# magicmouth-v0_1-ss.net
KiCad netlist of a schematic drawn in EAGLE
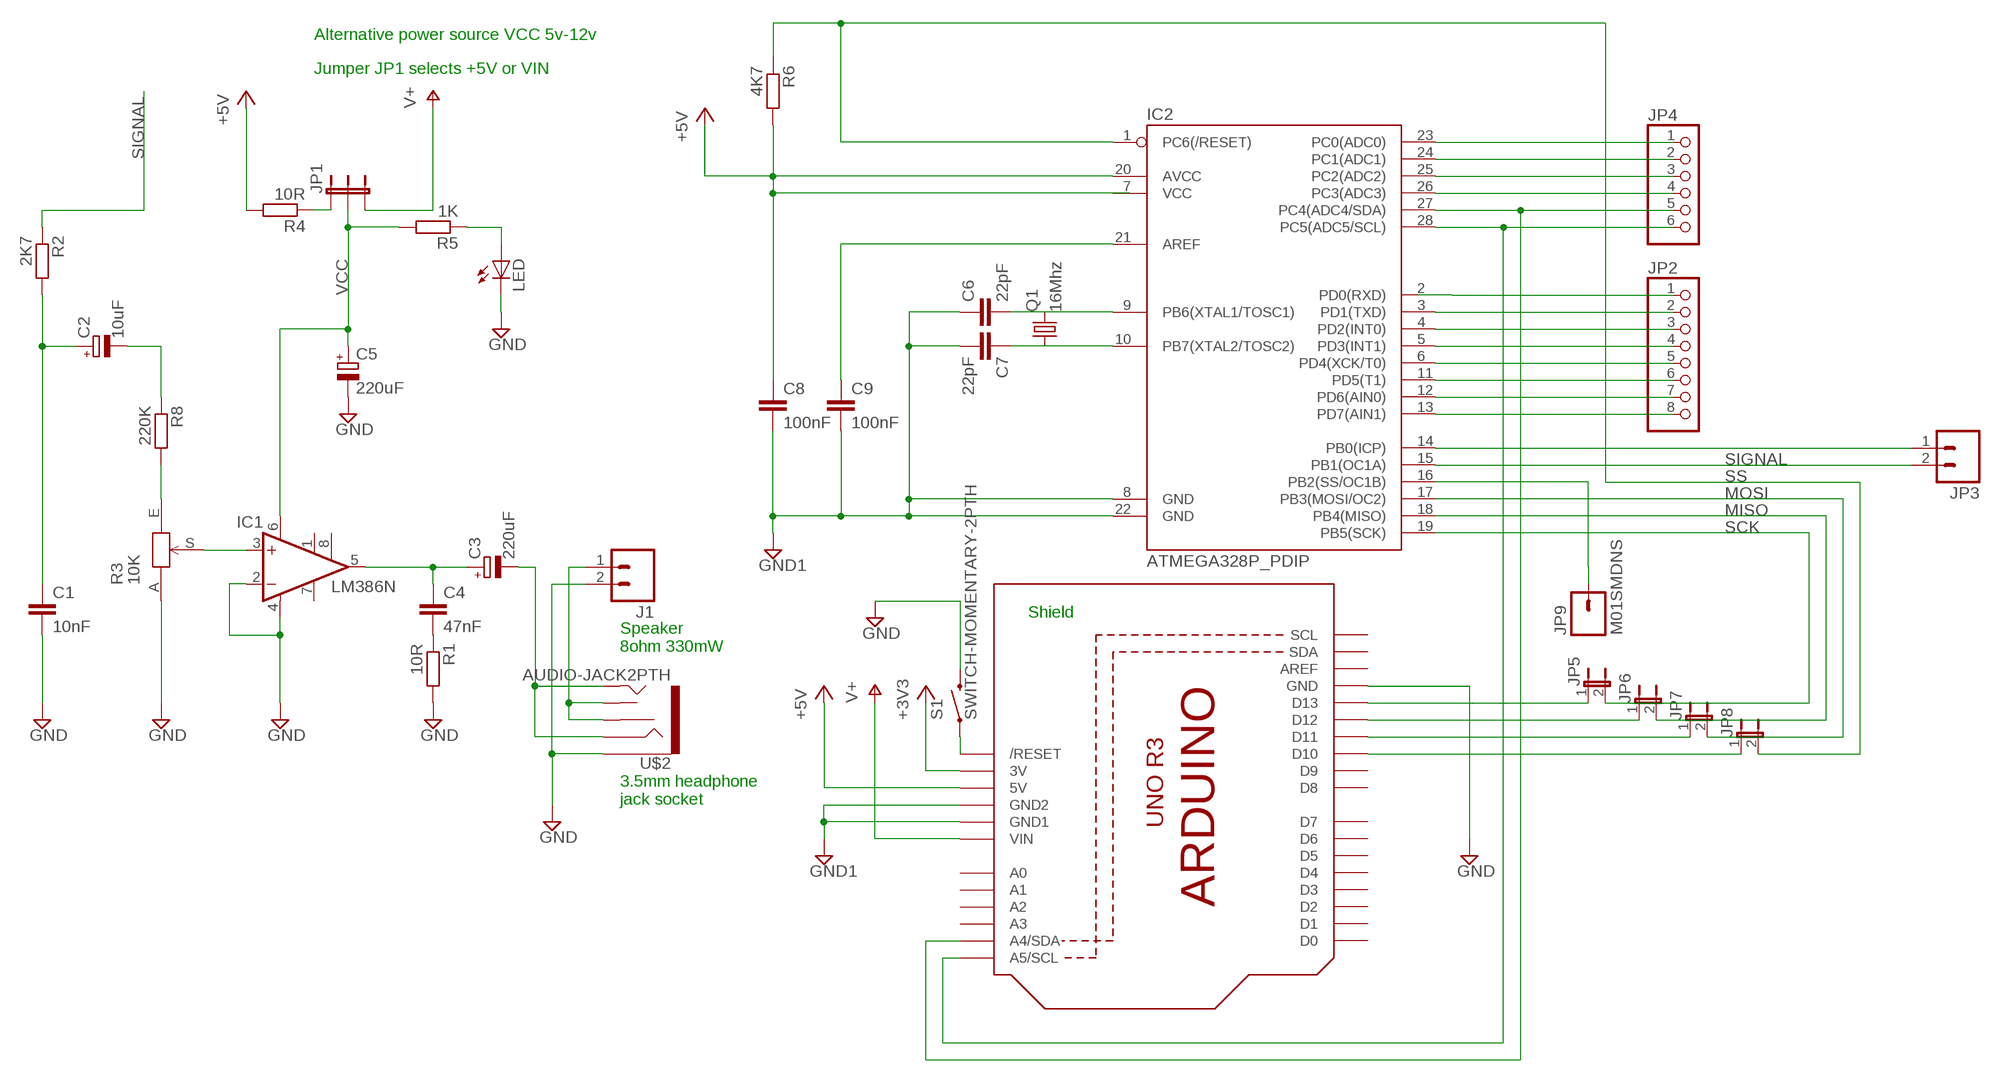
[diagram p0: schematic, sheet 1]

(export (version "E")
  (design (tool "Eeschema 10.0.6"))
  (components
    (comp (ref "C1")
      (value "10nF")
      (footprint "eagle-import:C050-025X075")
      (libsource (lib "eagle-import") (part "resistor_C-EU050-025X075"))
    )
    (comp (ref "C2")
      (value "10uF")
      (footprint "eagle-import:E2,5-7")
      (libsource (lib "eagle-import") (part "CPOL-EUE2.5-7"))
    )
    (comp (ref "C3")
      (value "220uF")
      (footprint "eagle-import:TT5D7L")
      (libsource (lib "eagle-import") (part "CPOL-EUTT5D7L"))
    )
    (comp (ref "C4")
      (value "47nF")
      (footprint "eagle-import:C050-025X075")
      (libsource (lib "eagle-import") (part "resistor_C-EU050-025X075"))
    )
    (comp (ref "C5")
      (value "220uF")
      (footprint "eagle-import:TT5D7L")
      (libsource (lib "eagle-import") (part "CPOL-EUTT5D7L"))
    )
    (comp (ref "C6")
      (value "22pF")
      (footprint "eagle-import:C025-025X050")
      (fields (field (name "CAPACITANCE") "22 pf"))
      (libsource (lib "eagle-import") (part "C-EU025-025X050"))
    )
    (comp (ref "C7")
      (value "22pF")
      (footprint "eagle-import:C025-025X050")
      (fields (field (name "CAPACITANCE") "22 pf"))
      (libsource (lib "eagle-import") (part "C-EU025-025X050"))
    )
    (comp (ref "C8")
      (value "100nF")
      (footprint "eagle-import:C025-025X050")
      (fields (field (name "CAPACITANCE") "10 nF"))
      (libsource (lib "eagle-import") (part "C-EU025-025X050"))
    )
    (comp (ref "C9")
      (value "100nF")
      (footprint "eagle-import:C025-025X050")
      (fields (field (name "CAPACITANCE") "100 nF"))
      (libsource (lib "eagle-import") (part "C-EU025-025X050"))
    )
    (comp (ref "IC1")
      (value "LM386N")
      (footprint "eagle-import:DIL08")
      (libsource (lib "eagle-import") (part "LM386?-N1"))
    )
    (comp (ref "IC2")
      (value "ATMEGA328P_PDIP")
      (footprint "eagle-import:DIL28-3")
      (libsource (lib "eagle-import") (part "ATMEGA328P_PDIP"))
    )
    (comp (ref "J1")
      (value "M023.5MM")
      (footprint "eagle-import:SCREWTERMINAL-3.5MM-2")
      (libsource (lib "eagle-import") (part "M023.5MM"))
    )
    (comp (ref "JP1")
      (value "JUMPER-3PTH")
      (footprint "eagle-import:1X03")
      (libsource (lib "eagle-import") (part "JUMPER-3PTH"))
    )
    (comp (ref "JP2")
      (value "PINHD-1X8CLEANBIG")
      (footprint "eagle-import:1X08-CLEANBIG")
      (libsource (lib "eagle-import") (part "PINHD-1X8CLEANBIG"))
    )
    (comp (ref "JP3")
      (value "M021X02_NO_SILK")
      (footprint "eagle-import:1X02_NO_SILK")
      (libsource (lib "eagle-import") (part "M021X02_NO_SILK"))
    )
    (comp (ref "JP4")
      (value "PINHD-1X6CB")
      (footprint "eagle-import:1X06-CLEANBIG")
      (libsource (lib "eagle-import") (part "PINHD-1X6CB"))
    )
    (comp (ref "JP5")
      (value "JUMPER-2PTH")
      (footprint "eagle-import:1X02")
      (libsource (lib "eagle-import") (part "JUMPER-2PTH"))
    )
    (comp (ref "JP6")
      (value "JUMPER-2PTH")
      (footprint "eagle-import:1X02")
      (libsource (lib "eagle-import") (part "JUMPER-2PTH"))
    )
    (comp (ref "JP7")
      (value "JUMPER-2PTH")
      (footprint "eagle-import:1X02")
      (libsource (lib "eagle-import") (part "JUMPER-2PTH"))
    )
    (comp (ref "JP8")
      (value "JUMPER-2PTH")
      (footprint "eagle-import:1X02")
      (libsource (lib "eagle-import") (part "JUMPER-2PTH"))
    )
    (comp (ref "JP9")
      (value "M01SMDNS")
      (footprint "eagle-import:1X01NS")
      (libsource (lib "eagle-import") (part "M01SMDNS"))
    )
    (comp (ref "LED")
      (value "LED3MM")
      (footprint "eagle-import:LED3MM")
      (libsource (lib "eagle-import") (part "LED3MM"))
    )
    (comp (ref "Q1")
      (value "16Mhz")
      (footprint "eagle-import:HC49_S")
      (libsource (lib "eagle-import") (part "CRYSTALHC49S"))
    )
    (comp (ref "R1")
      (value "10R")
      (footprint "eagle-import:0207_7")
      (libsource (lib "eagle-import") (part "resistor_R-EU_0207/7"))
    )
    (comp (ref "R2")
      (value "2K7")
      (footprint "eagle-import:0207_7")
      (libsource (lib "eagle-import") (part "R-EU_0207/7"))
    )
    (comp (ref "R3")
      (value "10K")
      (footprint "eagle-import:3352T")
      (libsource (lib "eagle-import") (part "TPOT3352"))
    )
    (comp (ref "R4")
      (value "10R")
      (footprint "eagle-import:0207_7")
      (libsource (lib "eagle-import") (part "R-EU_0207/7"))
    )
    (comp (ref "R5")
      (value "1K")
      (footprint "eagle-import:0207_7")
      (libsource (lib "eagle-import") (part "R-EU_0207/7"))
    )
    (comp (ref "R6")
      (value "4K7")
      (footprint "eagle-import:0207_7")
      (fields (field (name "RESISTANCE") "4K7"))
      (libsource (lib "eagle-import") (part "R-EU_0207/7"))
    )
    (comp (ref "R8")
      (value "220K")
      (footprint "eagle-import:0207_7")
      (libsource (lib "eagle-import") (part "R-EU_0207/7"))
    )
    (comp (ref "S1")
      (value "SWITCH-MOMENTARY-2PTH")
      (footprint "eagle-import:TACTILE-PTH")
      (libsource (lib "eagle-import") (part "SWITCH-MOMENTARY-2PTH"))
    )
    (comp (ref "U$2")
      (value "AUDIO-JACK2PTH")
      (footprint "eagle-import:AUDIO-JACK")
      (libsource (lib "eagle-import") (part "AUDIO-JACK2PTH"))
    )
    (comp (ref "U1")
      (value "ARDUINOR3-NOIOREF-NOTEXT")
      (footprint "eagle-import:ARDUINOR3-NOTEXT-NOIOREF")
      (libsource (lib "eagle-import") (part "ARDUINOR3-NOIOREF-NOTEXT"))
    )
  )
  (nets
    (net (code "1") (name "+3V3") (class "Default")
      (node (ref "U1") (pin "3V") (pinfunction "3V_3V") (pintype "power_in"))
    )
    (net (code "2") (name "+5V") (class "Default")
      (node (ref "C8") (pin "1") (pinfunction "1_1") (pintype "passive"))
      (node (ref "IC2") (pin "20") (pinfunction "AVCC_20") (pintype "bidirectional"))
      (node (ref "R4") (pin "2") (pinfunction "2_2") (pintype "passive"))
      (node (ref "R6") (pin "2") (pinfunction "2_2") (pintype "passive"))
      (node (ref "U1") (pin "5V") (pinfunction "5V_5V") (pintype "power_in"))
    )
    (net (code "3") (name "/MISO") (class "Default")
      (node (ref "IC2") (pin "18") (pinfunction "PB4(MISO)_18") (pintype "bidirectional"))
      (node (ref "JP6") (pin "2") (pinfunction "2_2") (pintype "passive"))
    )
    (net (code "4") (name "/MOSI") (class "Default")
      (node (ref "IC2") (pin "17") (pinfunction "PB3(MOSI/OC2)_17") (pintype "bidirectional"))
      (node (ref "JP7") (pin "2") (pinfunction "2_2") (pintype "passive"))
    )
    (net (code "5") (name "/SCK") (class "Default")
      (node (ref "IC2") (pin "19") (pinfunction "PB5(SCK)_19") (pintype "bidirectional"))
      (node (ref "JP5") (pin "2") (pinfunction "2_2") (pintype "passive"))
    )
    (net (code "6") (name "/SIGNAL") (class "Default")
      (node (ref "IC2") (pin "15") (pinfunction "PB1(OC1A)_15") (pintype "bidirectional"))
      (node (ref "JP3") (pin "2") (pinfunction "2_2") (pintype "passive"))
      (node (ref "R2") (pin "1") (pinfunction "1_1") (pintype "passive"))
    )
    (net (code "7") (name "/SS") (class "Default")
      (node (ref "IC2") (pin "1") (pinfunction "PC6(/RESET)_1") (pintype "bidirectional"))
      (node (ref "JP8") (pin "2") (pinfunction "2_2") (pintype "passive"))
      (node (ref "R6") (pin "1") (pinfunction "1_1") (pintype "passive"))
    )
    (net (code "8") (name "/VCC") (class "Default")
      (node (ref "C5") (pin "+") (pinfunction "+_+") (pintype "passive"))
      (node (ref "IC1") (pin "6") (pinfunction "VS_6") (pintype "power_in"))
      (node (ref "JP1") (pin "2") (pinfunction "2_2") (pintype "passive"))
      (node (ref "R5") (pin "2") (pinfunction "2_2") (pintype "passive"))
    )
    (net (code "9") (name "GND") (class "Default")
      (node (ref "C1") (pin "2") (pinfunction "2_2") (pintype "passive"))
      (node (ref "C5") (pin "-") (pinfunction "-_-") (pintype "passive"))
      (node (ref "IC1") (pin "2") (pinfunction "-IN_2") (pintype "input"))
      (node (ref "IC1") (pin "4") (pinfunction "GND_4") (pintype "power_in"))
      (node (ref "J1") (pin "2") (pinfunction "2_2") (pintype "passive"))
      (node (ref "LED") (pin "K") (pinfunction "C_K") (pintype "passive"))
      (node (ref "R1") (pin "2") (pinfunction "2_2") (pintype "passive"))
      (node (ref "R3") (pin "A") (pinfunction "A_A") (pintype "passive"))
      (node (ref "S1") (pin "3") (pinfunction "2_3") (pintype "passive"))
      (node (ref "U$2") (pin "SLEEVE") (pinfunction "SLEEVE_SLEEVE") (pintype "bidirectional"))
      (node (ref "U1") (pin "GND") (pinfunction "GND_GND") (pintype "power_in"))
    )
    (net (code "10") (name "GND1") (class "Default")
      (node (ref "C6") (pin "1") (pinfunction "1_1") (pintype "passive"))
      (node (ref "C7") (pin "2") (pinfunction "2_2") (pintype "passive"))
      (node (ref "C8") (pin "2") (pinfunction "2_2") (pintype "passive"))
      (node (ref "C9") (pin "2") (pinfunction "2_2") (pintype "passive"))
      (node (ref "IC2") (pin "22") (pinfunction "GND_22") (pintype "bidirectional"))
      (node (ref "IC2") (pin "8") (pinfunction "GND_8") (pintype "bidirectional"))
      (node (ref "U1") (pin "GND1") (pinfunction "GND1_GND1") (pintype "power_in"))
      (node (ref "U1") (pin "GND2") (pinfunction "GND2_GND2") (pintype "power_in"))
    )
    (net (code "11") (name "Net-(C1-Pad1)") (class "Default")
      (node (ref "C1") (pin "1") (pinfunction "1_1") (pintype "passive"))
      (node (ref "C2") (pin "+") (pinfunction "+_+") (pintype "passive"))
      (node (ref "R2") (pin "2") (pinfunction "2_2") (pintype "passive"))
    )
    (net (code "12") (name "Net-(C2-Pad-)") (class "Default")
      (node (ref "C2") (pin "-") (pinfunction "-_-") (pintype "passive"))
      (node (ref "R8") (pin "1") (pinfunction "1_1") (pintype "passive"))
    )
    (net (code "13") (name "Net-(C3-Pad-)") (class "Default")
      (node (ref "C3") (pin "-") (pinfunction "-_-") (pintype "passive"))
      (node (ref "U$2") (pin "RING") (pinfunction "RING_RING") (pintype "bidirectional"))
      (node (ref "U$2") (pin "TIP") (pinfunction "TIP_TIP") (pintype "bidirectional"))
    )
    (net (code "14") (name "Net-(C4-Pad2)") (class "Default")
      (node (ref "C4") (pin "2") (pinfunction "2_2") (pintype "passive"))
      (node (ref "R1") (pin "1") (pinfunction "1_1") (pintype "passive"))
    )
    (net (code "15") (name "Net-(IC1-+IN)") (class "Default")
      (node (ref "IC1") (pin "3") (pinfunction "+IN_3") (pintype "input"))
      (node (ref "R3") (pin "S") (pinfunction "S_S") (pintype "passive"))
    )
    (net (code "16") (name "Net-(IC1-OUT)") (class "Default")
      (node (ref "C3") (pin "+") (pinfunction "+_+") (pintype "passive"))
      (node (ref "C4") (pin "1") (pinfunction "1_1") (pintype "passive"))
      (node (ref "IC1") (pin "5") (pinfunction "OUT_5") (pintype "output"))
    )
    (net (code "17") (name "Net-(IC2-AREF)") (class "Default")
      (node (ref "C9") (pin "1") (pinfunction "1_1") (pintype "passive"))
      (node (ref "IC2") (pin "21") (pinfunction "AREF_21") (pintype "bidirectional"))
    )
    (net (code "18") (name "Net-(IC2-PB0(ICP))") (class "Default")
      (node (ref "IC2") (pin "14") (pinfunction "PB0(ICP)_14") (pintype "bidirectional"))
      (node (ref "JP3") (pin "1") (pinfunction "1_1") (pintype "passive"))
    )
    (net (code "19") (name "Net-(IC2-PB2(SS{slash}OC1B))") (class "Default")
      (node (ref "IC2") (pin "16") (pinfunction "PB2(SS/OC1B)_16") (pintype "bidirectional"))
      (node (ref "JP9") (pin "1") (pinfunction "1_1") (pintype "passive"))
    )
    (net (code "20") (name "Net-(IC2-PB6(XTAL1{slash}TOSC1))") (class "Default")
      (node (ref "C6") (pin "2") (pinfunction "2_2") (pintype "passive"))
      (node (ref "IC2") (pin "9") (pinfunction "PB6(XTAL1/TOSC1)_9") (pintype "bidirectional"))
      (node (ref "Q1") (pin "2") (pinfunction "2_2") (pintype "passive"))
    )
    (net (code "21") (name "Net-(IC2-PB7(XTAL2{slash}TOSC2))") (class "Default")
      (node (ref "C7") (pin "1") (pinfunction "1_1") (pintype "passive"))
      (node (ref "IC2") (pin "10") (pinfunction "PB7(XTAL2/TOSC2)_10") (pintype "bidirectional"))
      (node (ref "Q1") (pin "1") (pinfunction "1_1") (pintype "passive"))
    )
    (net (code "22") (name "Net-(IC2-PC0(ADC0))") (class "Default")
      (node (ref "IC2") (pin "23") (pinfunction "PC0(ADC0)_23") (pintype "bidirectional"))
      (node (ref "JP4") (pin "1") (pinfunction "1_1") (pintype "passive"))
    )
    (net (code "23") (name "Net-(IC2-PC1(ADC1))") (class "Default")
      (node (ref "IC2") (pin "24") (pinfunction "PC1(ADC1)_24") (pintype "bidirectional"))
      (node (ref "JP4") (pin "2") (pinfunction "2_2") (pintype "passive"))
    )
    (net (code "24") (name "Net-(IC2-PC2(ADC2))") (class "Default")
      (node (ref "IC2") (pin "25") (pinfunction "PC2(ADC2)_25") (pintype "bidirectional"))
      (node (ref "JP4") (pin "3") (pinfunction "3_3") (pintype "passive"))
    )
    (net (code "25") (name "Net-(IC2-PC3(ADC3))") (class "Default")
      (node (ref "IC2") (pin "26") (pinfunction "PC3(ADC3)_26") (pintype "bidirectional"))
      (node (ref "JP4") (pin "4") (pinfunction "4_4") (pintype "passive"))
    )
    (net (code "26") (name "Net-(IC2-PC4(ADC4{slash}SDA))") (class "Default")
      (node (ref "IC2") (pin "27") (pinfunction "PC4(ADC4/SDA)_27") (pintype "bidirectional"))
      (node (ref "JP4") (pin "5") (pinfunction "5_5") (pintype "passive"))
      (node (ref "U1") (pin "A4") (pinfunction "A4/SDA_A4") (pintype "bidirectional"))
    )
    (net (code "27") (name "Net-(IC2-PC5(ADC5{slash}SCL))") (class "Default")
      (node (ref "IC2") (pin "28") (pinfunction "PC5(ADC5/SCL)_28") (pintype "bidirectional"))
      (node (ref "JP4") (pin "6") (pinfunction "6_6") (pintype "passive"))
      (node (ref "U1") (pin "A5") (pinfunction "A5/SCL_A5") (pintype "bidirectional"))
    )
    (net (code "28") (name "Net-(IC2-PD1(TXD))") (class "Default")
      (node (ref "IC2") (pin "3") (pinfunction "PD1(TXD)_3") (pintype "bidirectional"))
      (node (ref "JP2") (pin "2") (pinfunction "2_2") (pintype "passive"))
    )
    (net (code "29") (name "Net-(IC2-PD2(INT0))") (class "Default")
      (node (ref "IC2") (pin "4") (pinfunction "PD2(INT0)_4") (pintype "bidirectional"))
      (node (ref "JP2") (pin "3") (pinfunction "3_3") (pintype "passive"))
    )
    (net (code "30") (name "Net-(IC2-PD3(INT1))") (class "Default")
      (node (ref "IC2") (pin "5") (pinfunction "PD3(INT1)_5") (pintype "bidirectional"))
      (node (ref "JP2") (pin "4") (pinfunction "4_4") (pintype "passive"))
    )
    (net (code "31") (name "Net-(IC2-PD4(XCK{slash}T0))") (class "Default")
      (node (ref "IC2") (pin "6") (pinfunction "PD4(XCK/T0)_6") (pintype "bidirectional"))
      (node (ref "JP2") (pin "5") (pinfunction "5_5") (pintype "passive"))
    )
    (net (code "32") (name "Net-(IC2-PD5(T1))") (class "Default")
      (node (ref "IC2") (pin "11") (pinfunction "PD5(T1)_11") (pintype "bidirectional"))
      (node (ref "JP2") (pin "6") (pinfunction "6_6") (pintype "passive"))
    )
    (net (code "33") (name "Net-(IC2-PD6(AIN0))") (class "Default")
      (node (ref "IC2") (pin "12") (pinfunction "PD6(AIN0)_12") (pintype "bidirectional"))
      (node (ref "JP2") (pin "7") (pinfunction "7_7") (pintype "passive"))
    )
    (net (code "34") (name "Net-(IC2-PD7(AIN1))") (class "Default")
      (node (ref "IC2") (pin "13") (pinfunction "PD7(AIN1)_13") (pintype "bidirectional"))
      (node (ref "JP2") (pin "8") (pinfunction "8_8") (pintype "passive"))
    )
    (net (code "35") (name "Net-(J1-Pad1)") (class "Default")
      (node (ref "J1") (pin "1") (pinfunction "1_1") (pintype "passive"))
      (node (ref "U$2") (pin "RSH") (pinfunction "RSH_RSH") (pintype "bidirectional"))
      (node (ref "U$2") (pin "TSH") (pinfunction "TSH_TSH") (pintype "bidirectional"))
    )
    (net (code "36") (name "Net-(JP1-Pad1)") (class "Default")
      (node (ref "JP1") (pin "1") (pinfunction "1_1") (pintype "passive"))
      (node (ref "R4") (pin "1") (pinfunction "1_1") (pintype "passive"))
    )
    (net (code "37") (name "Net-(JP5-Pad1)") (class "Default")
      (node (ref "JP5") (pin "1") (pinfunction "1_1") (pintype "passive"))
      (node (ref "U1") (pin "D13") (pinfunction "D13_D13") (pintype "bidirectional"))
    )
    (net (code "38") (name "Net-(JP6-Pad1)") (class "Default")
      (node (ref "JP6") (pin "1") (pinfunction "1_1") (pintype "passive"))
      (node (ref "U1") (pin "D12") (pinfunction "D12_D12") (pintype "bidirectional"))
    )
    (net (code "39") (name "Net-(JP7-Pad1)") (class "Default")
      (node (ref "JP7") (pin "1") (pinfunction "1_1") (pintype "passive"))
      (node (ref "U1") (pin "D11") (pinfunction "D11_D11") (pintype "bidirectional"))
    )
    (net (code "40") (name "Net-(JP8-Pad1)") (class "Default")
      (node (ref "JP8") (pin "1") (pinfunction "1_1") (pintype "passive"))
      (node (ref "U1") (pin "D10") (pinfunction "D10_D10") (pintype "bidirectional"))
    )
    (net (code "41") (name "Net-(LED-PadA)") (class "Default")
      (node (ref "LED") (pin "A") (pinfunction "A_A") (pintype "passive"))
      (node (ref "R5") (pin "1") (pinfunction "1_1") (pintype "passive"))
    )
    (net (code "42") (name "Net-(R3-PadE)") (class "Default")
      (node (ref "R3") (pin "E") (pinfunction "E_E") (pintype "passive"))
      (node (ref "R8") (pin "2") (pinfunction "2_2") (pintype "passive"))
    )
    (net (code "43") (name "Net-(U1-{slash}RESET)") (class "Default")
      (node (ref "S1") (pin "1") (pinfunction "1_1") (pintype "passive"))
      (node (ref "U1") (pin "RESET") (pinfunction "/RESET_RESET") (pintype "bidirectional"))
    )
    (net (code "44") (name "V+") (class "Default")
      (node (ref "JP1") (pin "3") (pinfunction "3_3") (pintype "passive"))
      (node (ref "U1") (pin "VIN") (pinfunction "VIN_VIN") (pintype "power_in"))
    )
    (net (code "45") (name "unconnected-(IC1-BYPASS-Pad7)") (class "Default")
      (node (ref "IC1") (pin "7") (pinfunction "BYPASS_7") (pintype "passive"))
    )
    (net (code "46") (name "unconnected-(IC1-GAIN-Pad1)") (class "Default")
      (node (ref "IC1") (pin "1") (pinfunction "GAIN_1") (pintype "passive"))
    )
    (net (code "47") (name "unconnected-(IC1-GAIN-Pad8)") (class "Default")
      (node (ref "IC1") (pin "8") (pinfunction "GAIN_8") (pintype "passive"))
    )
    (net (code "48") (name "unconnected-(IC2-PD0(RXD)-Pad2)") (class "Default")
      (node (ref "IC2") (pin "2") (pinfunction "PD0(RXD)_2") (pintype "bidirectional"))
    )
    (net (code "49") (name "unconnected-(IC2-VCC-Pad7)") (class "Default")
      (node (ref "IC2") (pin "7") (pinfunction "VCC_7") (pintype "bidirectional"))
    )
    (net (code "50") (name "unconnected-(JP2-Pad1)") (class "Default")
      (node (ref "JP2") (pin "1") (pinfunction "1_1") (pintype "passive"))
    )
    (net (code "51") (name "unconnected-(U1-PadA0)") (class "Default")
      (node (ref "U1") (pin "A0") (pinfunction "A0_A0") (pintype "bidirectional"))
    )
    (net (code "52") (name "unconnected-(U1-PadA1)") (class "Default")
      (node (ref "U1") (pin "A1") (pinfunction "A1_A1") (pintype "bidirectional"))
    )
    (net (code "53") (name "unconnected-(U1-PadA2)") (class "Default")
      (node (ref "U1") (pin "A2") (pinfunction "A2_A2") (pintype "bidirectional"))
    )
    (net (code "54") (name "unconnected-(U1-PadA3)") (class "Default")
      (node (ref "U1") (pin "A3") (pinfunction "A3_A3") (pintype "bidirectional"))
    )
    (net (code "55") (name "unconnected-(U1-PadAREF)") (class "Default")
      (node (ref "U1") (pin "AREF") (pinfunction "AREF_AREF") (pintype "bidirectional"))
    )
    (net (code "56") (name "unconnected-(U1-PadD0)") (class "Default")
      (node (ref "U1") (pin "D0") (pinfunction "D0_D0") (pintype "bidirectional"))
    )
    (net (code "57") (name "unconnected-(U1-PadD1)") (class "Default")
      (node (ref "U1") (pin "D1") (pinfunction "D1_D1") (pintype "bidirectional"))
    )
    (net (code "58") (name "unconnected-(U1-PadD2)") (class "Default")
      (node (ref "U1") (pin "D2") (pinfunction "D2_D2") (pintype "bidirectional"))
    )
    (net (code "59") (name "unconnected-(U1-PadD3)") (class "Default")
      (node (ref "U1") (pin "D3") (pinfunction "D3_D3") (pintype "bidirectional"))
    )
    (net (code "60") (name "unconnected-(U1-PadD4)") (class "Default")
      (node (ref "U1") (pin "D4") (pinfunction "D4_D4") (pintype "bidirectional"))
    )
    (net (code "61") (name "unconnected-(U1-PadD5)") (class "Default")
      (node (ref "U1") (pin "D5") (pinfunction "D5_D5") (pintype "bidirectional"))
    )
    (net (code "62") (name "unconnected-(U1-PadD6)") (class "Default")
      (node (ref "U1") (pin "D6") (pinfunction "D6_D6") (pintype "bidirectional"))
    )
    (net (code "63") (name "unconnected-(U1-PadD7)") (class "Default")
      (node (ref "U1") (pin "D7") (pinfunction "D7_D7") (pintype "bidirectional"))
    )
    (net (code "64") (name "unconnected-(U1-PadD8)") (class "Default")
      (node (ref "U1") (pin "D8") (pinfunction "D8_D8") (pintype "bidirectional"))
    )
    (net (code "65") (name "unconnected-(U1-PadD9)") (class "Default")
      (node (ref "U1") (pin "D9") (pinfunction "D9_D9") (pintype "bidirectional"))
    )
    (net (code "66") (name "unconnected-(U1-PadSCL)") (class "Default")
      (node (ref "U1") (pin "SCL") (pinfunction "SCL_SCL") (pintype "bidirectional"))
    )
    (net (code "67") (name "unconnected-(U1-PadSDA)") (class "Default")
      (node (ref "U1") (pin "SDA") (pinfunction "SDA_SDA") (pintype "bidirectional"))
    )
  )
)
